# Filter_Capacitors_-_Port_F.net
KiCad netlist of a schematic drawn in Altium Designer
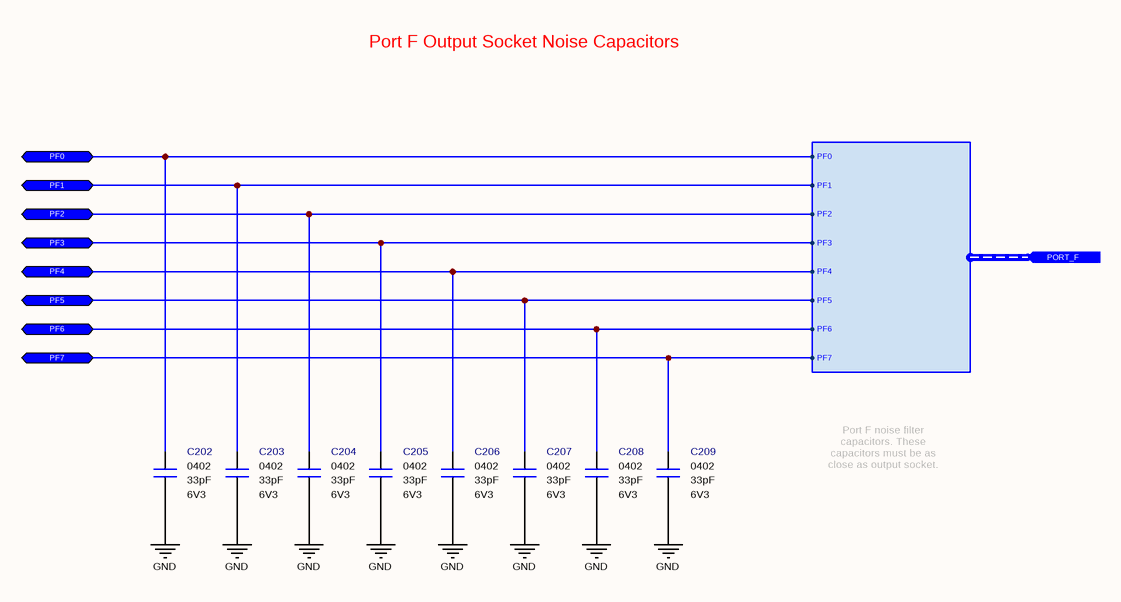
[diagram p0: Filter Capacitors - Port F.SchDoc]

(export (version "E")
  (design (tool "Eeschema 10.0.6"))
  (components
    (comp (ref "C202")
      (value "33pF")
      (footprint "CAPACITOR_0402")
      (description "Capacitor - 33pF [0402] (Ceramic)")
      (fields
        (field (name "TOLERANCE") "10%")
        (field (name "CASE") "0402")
        (field (name "VOLTAGE") "6V3")
        (field (name "MANUFACTURER PART NUMBER") "C0402C330J9RACAUTO")
      )
      (libsource (lib "Ovoo_Library") (part "Capacitor - 33pF [0402-6V3]"))
    )
    (comp (ref "C203")
      (value "33pF")
      (footprint "CAPACITOR_0402")
      (description "Capacitor - 33pF [0402] (Ceramic)")
      (fields
        (field (name "TOLERANCE") "10%")
        (field (name "CASE") "0402")
        (field (name "VOLTAGE") "6V3")
        (field (name "MANUFACTURER PART NUMBER") "C0402C330J9RACAUTO")
      )
      (libsource (lib "Ovoo_Library") (part "Capacitor - 33pF [0402-6V3]"))
    )
    (comp (ref "C204")
      (value "33pF")
      (footprint "CAPACITOR_0402")
      (description "Capacitor - 33pF [0402] (Ceramic)")
      (fields
        (field (name "TOLERANCE") "10%")
        (field (name "CASE") "0402")
        (field (name "VOLTAGE") "6V3")
        (field (name "MANUFACTURER PART NUMBER") "C0402C330J9RACAUTO")
      )
      (libsource (lib "Ovoo_Library") (part "Capacitor - 33pF [0402-6V3]"))
    )
    (comp (ref "C205")
      (value "33pF")
      (footprint "CAPACITOR_0402")
      (description "Capacitor - 33pF [0402] (Ceramic)")
      (fields
        (field (name "TOLERANCE") "10%")
        (field (name "CASE") "0402")
        (field (name "VOLTAGE") "6V3")
        (field (name "MANUFACTURER PART NUMBER") "C0402C330J9RACAUTO")
      )
      (libsource (lib "Ovoo_Library") (part "Capacitor - 33pF [0402-6V3]"))
    )
    (comp (ref "C206")
      (value "33pF")
      (footprint "CAPACITOR_0402")
      (description "Capacitor - 33pF [0402] (Ceramic)")
      (fields
        (field (name "TOLERANCE") "10%")
        (field (name "CASE") "0402")
        (field (name "VOLTAGE") "6V3")
        (field (name "MANUFACTURER PART NUMBER") "C0402C330J9RACAUTO")
      )
      (libsource (lib "Ovoo_Library") (part "Capacitor - 33pF [0402-6V3]"))
    )
    (comp (ref "C207")
      (value "33pF")
      (footprint "CAPACITOR_0402")
      (description "Capacitor - 33pF [0402] (Ceramic)")
      (fields
        (field (name "TOLERANCE") "10%")
        (field (name "CASE") "0402")
        (field (name "VOLTAGE") "6V3")
        (field (name "MANUFACTURER PART NUMBER") "C0402C330J9RACAUTO")
      )
      (libsource (lib "Ovoo_Library") (part "Capacitor - 33pF [0402-6V3]"))
    )
    (comp (ref "C208")
      (value "33pF")
      (footprint "CAPACITOR_0402")
      (description "Capacitor - 33pF [0402] (Ceramic)")
      (fields
        (field (name "TOLERANCE") "10%")
        (field (name "CASE") "0402")
        (field (name "VOLTAGE") "6V3")
        (field (name "MANUFACTURER PART NUMBER") "C0402C330J9RACAUTO")
      )
      (libsource (lib "Ovoo_Library") (part "Capacitor - 33pF [0402-6V3]"))
    )
    (comp (ref "C209")
      (value "33pF")
      (footprint "CAPACITOR_0402")
      (description "Capacitor - 33pF [0402] (Ceramic)")
      (fields
        (field (name "TOLERANCE") "10%")
        (field (name "CASE") "0402")
        (field (name "VOLTAGE") "6V3")
        (field (name "MANUFACTURER PART NUMBER") "C0402C330J9RACAUTO")
      )
      (libsource (lib "Ovoo_Library") (part "Capacitor - 33pF [0402-6V3]"))
    )
  )
  (nets
    (net (code "2") (name "/PF0") (class "Default")
      (node (ref "C202") (pin "2") (pinfunction "2_2") (pintype "passive"))
    )
    (net (code "3") (name "/PF1") (class "Default")
      (node (ref "C203") (pin "2") (pinfunction "2_2") (pintype "passive"))
    )
    (net (code "4") (name "/PF2") (class "Default")
      (node (ref "C204") (pin "2") (pinfunction "2_2") (pintype "passive"))
    )
    (net (code "5") (name "/PF3") (class "Default")
      (node (ref "C205") (pin "2") (pinfunction "2_2") (pintype "passive"))
    )
    (net (code "6") (name "/PF4") (class "Default")
      (node (ref "C206") (pin "2") (pinfunction "2_2") (pintype "passive"))
    )
    (net (code "7") (name "/PF5") (class "Default")
      (node (ref "C207") (pin "2") (pinfunction "2_2") (pintype "passive"))
    )
    (net (code "8") (name "/PF6") (class "Default")
      (node (ref "C208") (pin "2") (pinfunction "2_2") (pintype "passive"))
    )
    (net (code "9") (name "/PF7") (class "Default")
      (node (ref "C209") (pin "2") (pinfunction "2_2") (pintype "passive"))
    )
    (net (code "11") (name "GND") (class "Default")
      (node (ref "C202") (pin "1") (pinfunction "1_1") (pintype "passive"))
      (node (ref "C203") (pin "1") (pinfunction "1_1") (pintype "passive"))
      (node (ref "C204") (pin "1") (pinfunction "1_1") (pintype "passive"))
      (node (ref "C205") (pin "1") (pinfunction "1_1") (pintype "passive"))
      (node (ref "C206") (pin "1") (pinfunction "1_1") (pintype "passive"))
      (node (ref "C207") (pin "1") (pinfunction "1_1") (pintype "passive"))
      (node (ref "C208") (pin "1") (pinfunction "1_1") (pintype "passive"))
      (node (ref "C209") (pin "1") (pinfunction "1_1") (pintype "passive"))
    )
  )
)
